# backplane_v1_0-smd.net
KiCad netlist of a schematic drawn in EAGLE
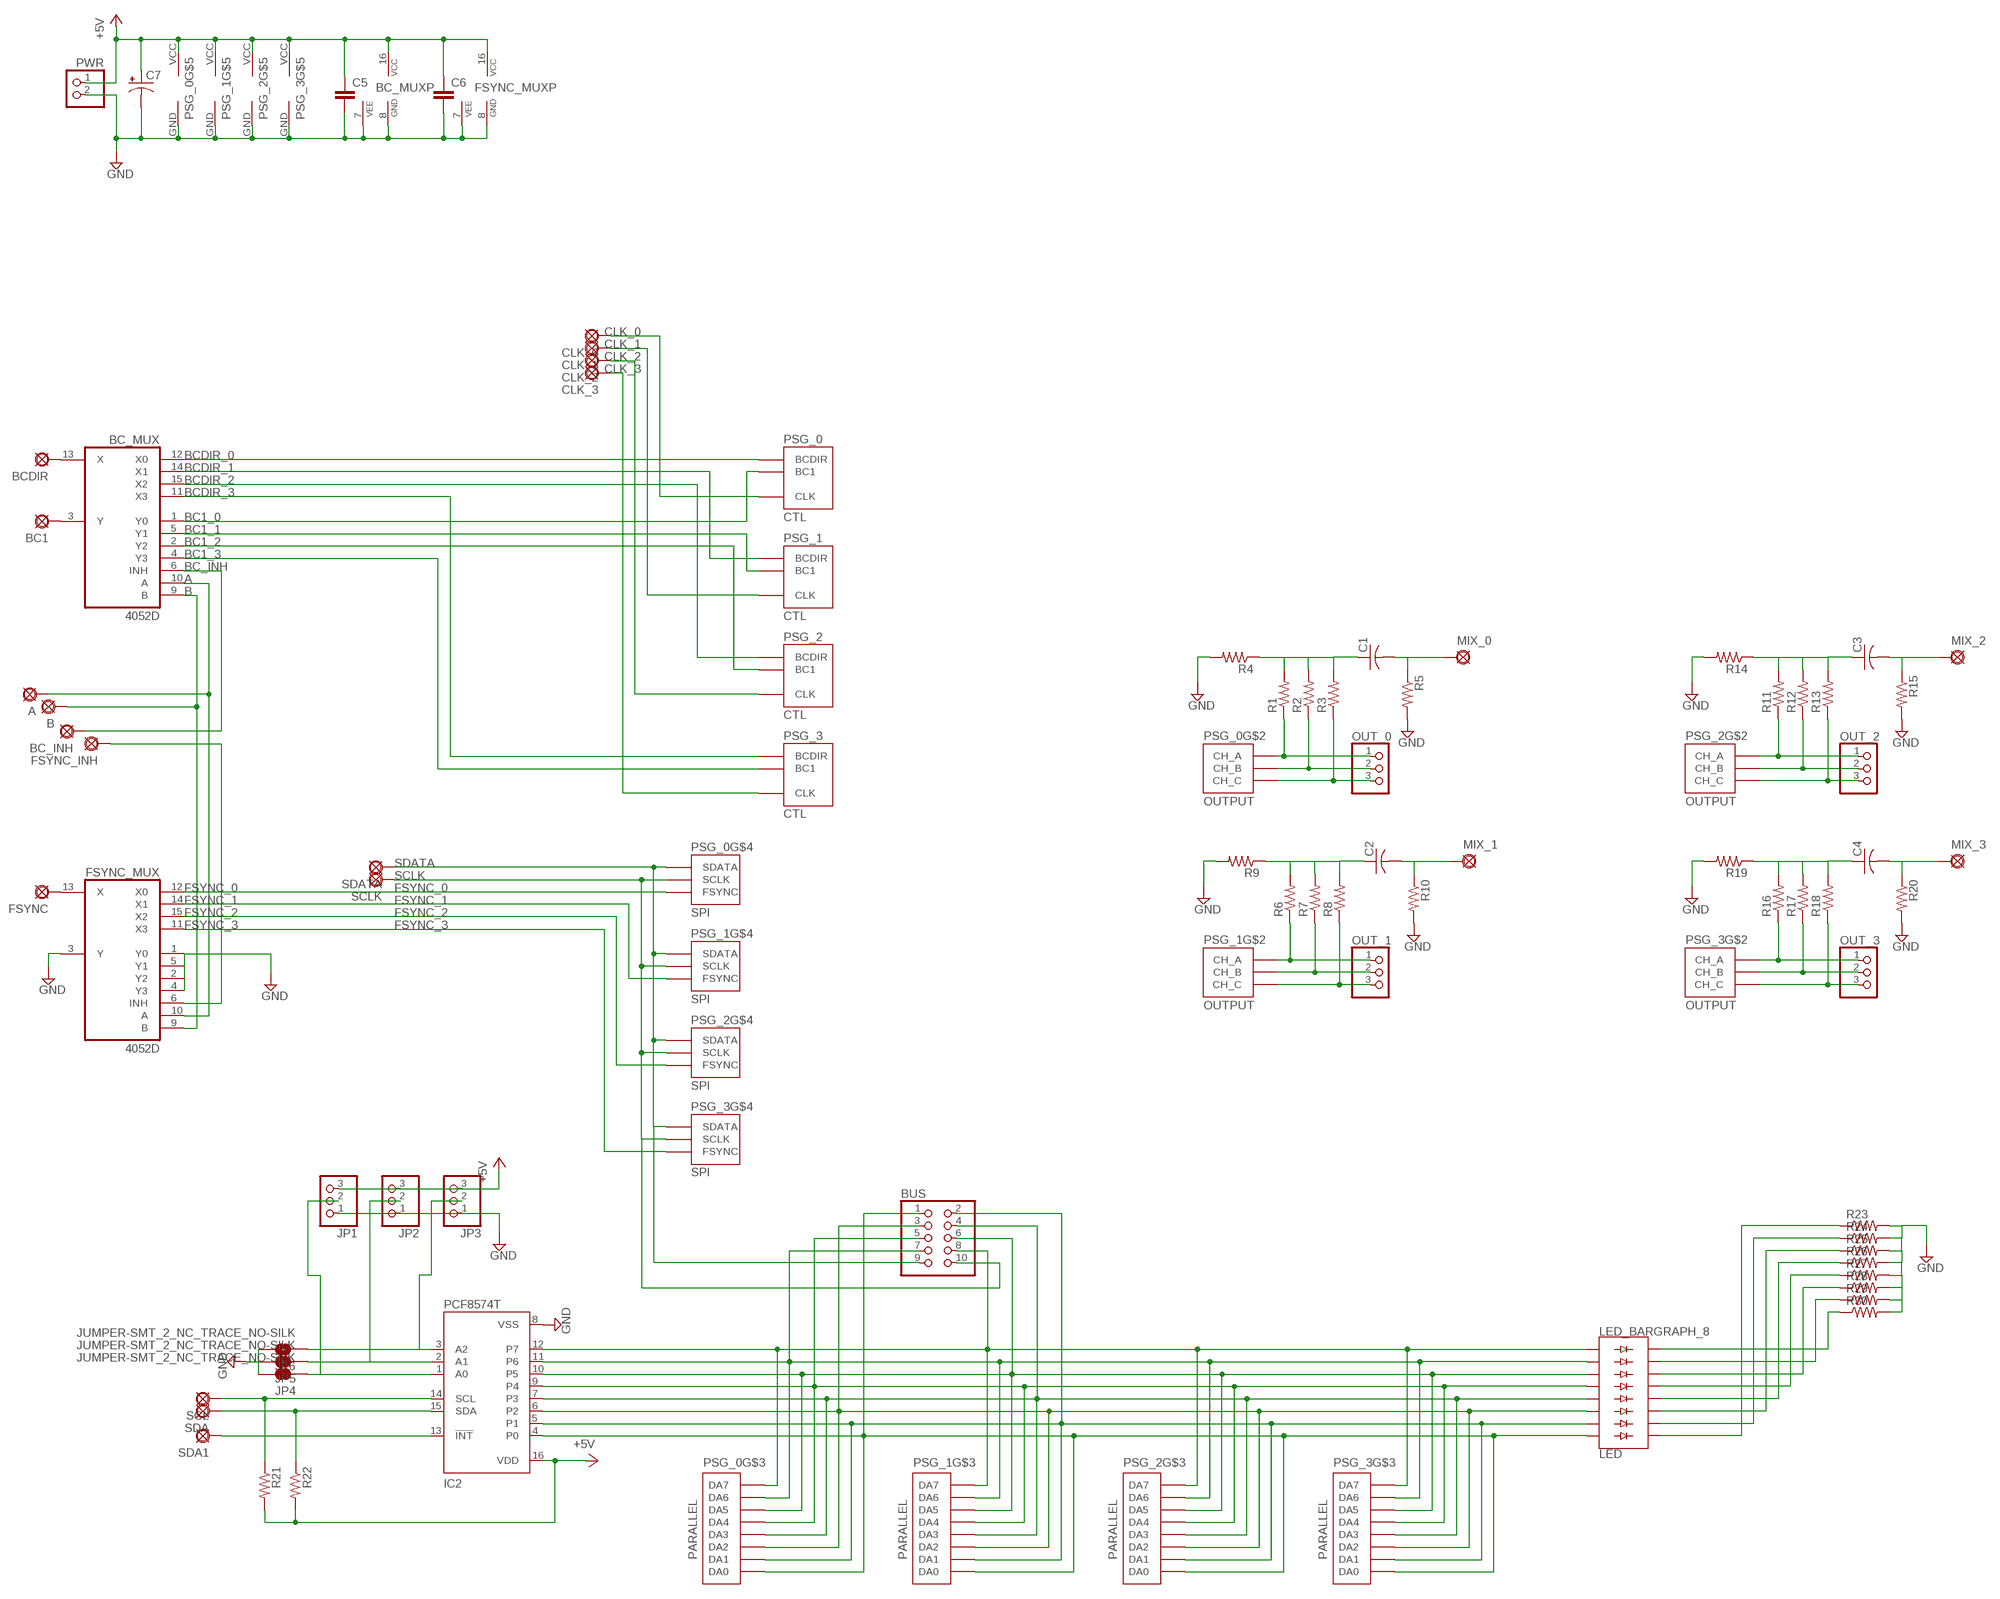
[diagram p0: schematic, sheet 1]

(export (version "E")
  (design (tool "Eeschema 10.0.6"))
  (components
    (comp (ref "A")
      (value "PAD")
      (footprint "eagle-import:SQUARE")
      (libsource (lib "eagle-import") (part "PAD"))
    )
    (comp (ref "B")
      (value "PAD")
      (footprint "eagle-import:SQUARE")
      (libsource (lib "eagle-import") (part "PAD"))
    )
    (comp (ref "BC1")
      (value "PAD")
      (footprint "eagle-import:SQUARE")
      (libsource (lib "eagle-import") (part "PAD"))
    )
    (comp (ref "BCDIR")
      (value "PAD")
      (footprint "eagle-import:SQUARE")
      (libsource (lib "eagle-import") (part "PAD"))
    )
    (comp (ref "BC_INH")
      (value "PAD")
      (footprint "eagle-import:SQUARE")
      (libsource (lib "eagle-import") (part "PAD"))
    )
    (comp (ref "BC_MUX")
      (value "4052D")
      (footprint "eagle-import:SO16")
      (libsource (lib "eagle-import") (part "4052D"))
    )
    (comp (ref "BUS")
      (value "PINHD-2X5IDC")
      (footprint "eagle-import:10PIN_IDC")
      (libsource (lib "eagle-import") (part "PINHD-2X5IDC"))
    )
    (comp (ref "C1")
      (value "C-USC0805")
      (footprint "eagle-import:C0805")
      (libsource (lib "eagle-import") (part "C-USC0805"))
    )
    (comp (ref "C2")
      (value "C-USC0805")
      (footprint "eagle-import:C0805")
      (libsource (lib "eagle-import") (part "C-USC0805"))
    )
    (comp (ref "C3")
      (value "C-USC0805")
      (footprint "eagle-import:C0805")
      (libsource (lib "eagle-import") (part "C-USC0805"))
    )
    (comp (ref "C4")
      (value "C-USC0805")
      (footprint "eagle-import:C0805")
      (libsource (lib "eagle-import") (part "C-USC0805"))
    )
    (comp (ref "C5")
      (value "050X030_0251")
      (footprint "eagle-import:050X030_025")
      (libsource (lib "eagle-import") (part "050X030_0251"))
    )
    (comp (ref "C6")
      (value "050X030_0251")
      (footprint "eagle-import:050X030_025")
      (libsource (lib "eagle-import") (part "050X030_0251"))
    )
    (comp (ref "C7")
      (value "0631")
      (footprint "eagle-import:063_025")
      (libsource (lib "eagle-import") (part "0631"))
    )
    (comp (ref "CLK_0")
      (value "PAD")
      (footprint "eagle-import:SQUARE")
      (libsource (lib "eagle-import") (part "PAD"))
    )
    (comp (ref "CLK_1")
      (value "PAD")
      (footprint "eagle-import:SQUARE")
      (libsource (lib "eagle-import") (part "PAD"))
    )
    (comp (ref "CLK_2")
      (value "PAD")
      (footprint "eagle-import:SQUARE")
      (libsource (lib "eagle-import") (part "PAD"))
    )
    (comp (ref "CLK_3")
      (value "PAD")
      (footprint "eagle-import:SQUARE")
      (libsource (lib "eagle-import") (part "PAD"))
    )
    (comp (ref "FSYNC")
      (value "PAD")
      (footprint "eagle-import:SQUARE")
      (libsource (lib "eagle-import") (part "PAD"))
    )
    (comp (ref "FSYNC_INH")
      (value "PAD")
      (footprint "eagle-import:SQUARE")
      (libsource (lib "eagle-import") (part "PAD"))
    )
    (comp (ref "FSYNC_MUX")
      (value "4052D")
      (footprint "eagle-import:SO16")
      (libsource (lib "eagle-import") (part "4052D"))
    )
    (comp (ref "IC2")
      (value "PCF8574T")
      (footprint "eagle-import:SO16W")
      (fields (field (name "MPN") "PCF8574T/3,512"))
      (libsource (lib "eagle-import") (part "PCF8574T"))
    )
    (comp (ref "JP1")
      (value "PINHD-1X3")
      (footprint "eagle-import:1X03")
      (libsource (lib "eagle-import") (part "PINHD-1X3"))
    )
    (comp (ref "JP2")
      (value "PINHD-1X3")
      (footprint "eagle-import:1X03")
      (libsource (lib "eagle-import") (part "PINHD-1X3"))
    )
    (comp (ref "JP3")
      (value "PINHD-1X3")
      (footprint "eagle-import:1X03")
      (libsource (lib "eagle-import") (part "PINHD-1X3"))
    )
    (comp (ref "JP4")
      (value "JUMPER-SMT_2_NC_TRACE_NO-SILK")
      (footprint "eagle-import:SMT-JUMPER_2_NC_TRACE_NO-SILK")
      (libsource (lib "eagle-import") (part "JUMPER-SMT_2_NC_TRACE_NO-SILK"))
    )
    (comp (ref "JP5")
      (value "JUMPER-SMT_2_NC_TRACE_NO-SILK")
      (footprint "eagle-import:SMT-JUMPER_2_NC_TRACE_NO-SILK")
      (libsource (lib "eagle-import") (part "JUMPER-SMT_2_NC_TRACE_NO-SILK"))
    )
    (comp (ref "JP6")
      (value "JUMPER-SMT_2_NC_TRACE_NO-SILK")
      (footprint "eagle-import:SMT-JUMPER_2_NC_TRACE_NO-SILK")
      (libsource (lib "eagle-import") (part "JUMPER-SMT_2_NC_TRACE_NO-SILK"))
    )
    (comp (ref "LED")
      (value "LED_BARGRAPH_8")
      (footprint "eagle-import:LED_BARGRAPH_8")
      (libsource (lib "eagle-import") (part "LED_BARGRAPH_8"))
    )
    (comp (ref "MIX_0")
      (value "PAD")
      (footprint "eagle-import:SQUARE")
      (libsource (lib "eagle-import") (part "PAD"))
    )
    (comp (ref "MIX_1")
      (value "PAD")
      (footprint "eagle-import:SQUARE")
      (libsource (lib "eagle-import") (part "PAD"))
    )
    (comp (ref "MIX_2")
      (value "PAD")
      (footprint "eagle-import:SQUARE")
      (libsource (lib "eagle-import") (part "PAD"))
    )
    (comp (ref "MIX_3")
      (value "PAD")
      (footprint "eagle-import:SQUARE")
      (libsource (lib "eagle-import") (part "PAD"))
    )
    (comp (ref "OUT_0")
      (value "PINHD-1X3")
      (footprint "eagle-import:1X03")
      (libsource (lib "eagle-import") (part "PINHD-1X3"))
    )
    (comp (ref "OUT_1")
      (value "PINHD-1X3")
      (footprint "eagle-import:1X03")
      (libsource (lib "eagle-import") (part "PINHD-1X3"))
    )
    (comp (ref "OUT_2")
      (value "PINHD-1X3")
      (footprint "eagle-import:1X03")
      (libsource (lib "eagle-import") (part "PINHD-1X3"))
    )
    (comp (ref "OUT_3")
      (value "PINHD-1X3")
      (footprint "eagle-import:1X03")
      (libsource (lib "eagle-import") (part "PINHD-1X3"))
    )
    (comp (ref "PSG_0")
      (value "PSG_DAUGHTER")
      (footprint "eagle-import:PSG_DAUGHTER")
      (libsource (lib "eagle-import") (part "PSG_DAUGHTER"))
    )
    (comp (ref "PSG_1")
      (value "PSG_DAUGHTER")
      (footprint "eagle-import:PSG_DAUGHTER")
      (libsource (lib "eagle-import") (part "PSG_DAUGHTER"))
    )
    (comp (ref "PSG_2")
      (value "PSG_DAUGHTER")
      (footprint "eagle-import:PSG_DAUGHTER")
      (libsource (lib "eagle-import") (part "PSG_DAUGHTER"))
    )
    (comp (ref "PSG_3")
      (value "PSG_DAUGHTER")
      (footprint "eagle-import:PSG_DAUGHTER")
      (libsource (lib "eagle-import") (part "PSG_DAUGHTER"))
    )
    (comp (ref "PWR")
      (value "PINHD-1X2")
      (footprint "eagle-import:1X02")
      (libsource (lib "eagle-import") (part "PINHD-1X2"))
    )
    (comp (ref "R1")
      (value "R-US_R0805")
      (footprint "eagle-import:R0805")
      (libsource (lib "eagle-import") (part "R-US_R0805"))
    )
    (comp (ref "R2")
      (value "R-US_R0805")
      (footprint "eagle-import:R0805")
      (libsource (lib "eagle-import") (part "R-US_R0805"))
    )
    (comp (ref "R3")
      (value "R-US_R0805")
      (footprint "eagle-import:R0805")
      (libsource (lib "eagle-import") (part "R-US_R0805"))
    )
    (comp (ref "R4")
      (value "R-US_R0805")
      (footprint "eagle-import:R0805")
      (libsource (lib "eagle-import") (part "R-US_R0805"))
    )
    (comp (ref "R5")
      (value "R-US_R0805")
      (footprint "eagle-import:R0805")
      (libsource (lib "eagle-import") (part "R-US_R0805"))
    )
    (comp (ref "R6")
      (value "R-US_R0805")
      (footprint "eagle-import:R0805")
      (libsource (lib "eagle-import") (part "R-US_R0805"))
    )
    (comp (ref "R7")
      (value "R-US_R0805")
      (footprint "eagle-import:R0805")
      (libsource (lib "eagle-import") (part "R-US_R0805"))
    )
    (comp (ref "R8")
      (value "R-US_R0805")
      (footprint "eagle-import:R0805")
      (libsource (lib "eagle-import") (part "R-US_R0805"))
    )
    (comp (ref "R9")
      (value "R-US_R0805")
      (footprint "eagle-import:R0805")
      (libsource (lib "eagle-import") (part "R-US_R0805"))
    )
    (comp (ref "R10")
      (value "R-US_R0805")
      (footprint "eagle-import:R0805")
      (libsource (lib "eagle-import") (part "R-US_R0805"))
    )
    (comp (ref "R11")
      (value "R-US_R0805")
      (footprint "eagle-import:R0805")
      (libsource (lib "eagle-import") (part "R-US_R0805"))
    )
    (comp (ref "R12")
      (value "R-US_R0805")
      (footprint "eagle-import:R0805")
      (libsource (lib "eagle-import") (part "R-US_R0805"))
    )
    (comp (ref "R13")
      (value "R-US_R0805")
      (footprint "eagle-import:R0805")
      (libsource (lib "eagle-import") (part "R-US_R0805"))
    )
    (comp (ref "R14")
      (value "R-US_R0805")
      (footprint "eagle-import:R0805")
      (libsource (lib "eagle-import") (part "R-US_R0805"))
    )
    (comp (ref "R15")
      (value "R-US_R0805")
      (footprint "eagle-import:R0805")
      (libsource (lib "eagle-import") (part "R-US_R0805"))
    )
    (comp (ref "R16")
      (value "R-US_R0805")
      (footprint "eagle-import:R0805")
      (libsource (lib "eagle-import") (part "R-US_R0805"))
    )
    (comp (ref "R17")
      (value "R-US_R0805")
      (footprint "eagle-import:R0805")
      (libsource (lib "eagle-import") (part "R-US_R0805"))
    )
    (comp (ref "R18")
      (value "R-US_R0805")
      (footprint "eagle-import:R0805")
      (libsource (lib "eagle-import") (part "R-US_R0805"))
    )
    (comp (ref "R19")
      (value "R-US_R0805")
      (footprint "eagle-import:R0805")
      (libsource (lib "eagle-import") (part "R-US_R0805"))
    )
    (comp (ref "R20")
      (value "R-US_R0805")
      (footprint "eagle-import:R0805")
      (libsource (lib "eagle-import") (part "R-US_R0805"))
    )
    (comp (ref "R21")
      (value "R-US_R0805")
      (footprint "eagle-import:R0805")
      (libsource (lib "eagle-import") (part "R-US_R0805"))
    )
    (comp (ref "R22")
      (value "R-US_R0805")
      (footprint "eagle-import:R0805")
      (libsource (lib "eagle-import") (part "R-US_R0805"))
    )
    (comp (ref "R23")
      (value "R-US_R0805")
      (footprint "eagle-import:R0805")
      (libsource (lib "eagle-import") (part "R-US_R0805"))
    )
    (comp (ref "R24")
      (value "R-US_R0805")
      (footprint "eagle-import:R0805")
      (libsource (lib "eagle-import") (part "R-US_R0805"))
    )
    (comp (ref "R25")
      (value "R-US_R0805")
      (footprint "eagle-import:R0805")
      (libsource (lib "eagle-import") (part "R-US_R0805"))
    )
    (comp (ref "R26")
      (value "R-US_R0805")
      (footprint "eagle-import:R0805")
      (libsource (lib "eagle-import") (part "R-US_R0805"))
    )
    (comp (ref "R27")
      (value "R-US_R0805")
      (footprint "eagle-import:R0805")
      (libsource (lib "eagle-import") (part "R-US_R0805"))
    )
    (comp (ref "R28")
      (value "R-US_R0805")
      (footprint "eagle-import:R0805")
      (libsource (lib "eagle-import") (part "R-US_R0805"))
    )
    (comp (ref "R29")
      (value "R-US_R0805")
      (footprint "eagle-import:R0805")
      (libsource (lib "eagle-import") (part "R-US_R0805"))
    )
    (comp (ref "R30")
      (value "R-US_R0805")
      (footprint "eagle-import:R0805")
      (libsource (lib "eagle-import") (part "R-US_R0805"))
    )
    (comp (ref "SCL")
      (value "PAD")
      (footprint "eagle-import:SQUARE")
      (libsource (lib "eagle-import") (part "PAD"))
    )
    (comp (ref "SCLK")
      (value "PAD")
      (footprint "eagle-import:SQUARE")
      (libsource (lib "eagle-import") (part "PAD"))
    )
    (comp (ref "SDA")
      (value "PAD")
      (footprint "eagle-import:SQUARE")
      (libsource (lib "eagle-import") (part "PAD"))
    )
    (comp (ref "SDA1")
      (value "PAD")
      (footprint "eagle-import:SQUARE")
      (libsource (lib "eagle-import") (part "PAD"))
    )
    (comp (ref "SDATA")
      (value "PAD")
      (footprint "eagle-import:SQUARE")
      (libsource (lib "eagle-import") (part "PAD"))
    )
  )
  (nets
    (net (code "1") (name "+5V") (class "Default")
      (node (ref "BC_MUX") (pin "16") (pinfunction "VCC_16") (pintype "power_in"))
      (node (ref "C5") (pin "1") (pinfunction "1_1") (pintype "passive"))
      (node (ref "C6") (pin "1") (pinfunction "1_1") (pintype "passive"))
      (node (ref "C7") (pin "+") (pinfunction "+_+") (pintype "passive"))
      (node (ref "FSYNC_MUX") (pin "16") (pinfunction "VCC_16") (pintype "power_in"))
      (node (ref "IC2") (pin "16") (pinfunction "VDD_16") (pintype "power_in"))
      (node (ref "JP1") (pin "3") (pinfunction "3_3") (pintype "passive"))
      (node (ref "JP2") (pin "3") (pinfunction "3_3") (pintype "passive"))
      (node (ref "JP3") (pin "3") (pinfunction "3_3") (pintype "passive"))
      (node (ref "PSG_0") (pin "VCC") (pinfunction "VCC_VCC") (pintype "power_in"))
      (node (ref "PSG_1") (pin "VCC") (pinfunction "VCC_VCC") (pintype "power_in"))
      (node (ref "PSG_2") (pin "VCC") (pinfunction "VCC_VCC") (pintype "power_in"))
      (node (ref "PSG_3") (pin "VCC") (pinfunction "VCC_VCC") (pintype "power_in"))
      (node (ref "PWR") (pin "1") (pinfunction "1_1") (pintype "passive"))
      (node (ref "R21") (pin "2") (pinfunction "2_2") (pintype "passive"))
      (node (ref "R22") (pin "2") (pinfunction "2_2") (pintype "passive"))
    )
    (net (code "2") (name "/A") (class "Default")
      (node (ref "A") (pin "1") (pinfunction "PAD_1") (pintype "passive"))
      (node (ref "BC_MUX") (pin "10") (pinfunction "A_10") (pintype "input"))
      (node (ref "FSYNC_MUX") (pin "10") (pinfunction "A_10") (pintype "input"))
    )
    (net (code "3") (name "/B") (class "Default")
      (node (ref "B") (pin "1") (pinfunction "PAD_1") (pintype "passive"))
      (node (ref "BC_MUX") (pin "9") (pinfunction "B_9") (pintype "input"))
      (node (ref "FSYNC_MUX") (pin "9") (pinfunction "B_9") (pintype "input"))
    )
    (net (code "4") (name "/BC1_0") (class "Default")
      (node (ref "BC_MUX") (pin "1") (pinfunction "Y0_1") (pintype "bidirectional"))
      (node (ref "PSG_0") (pin "BC1") (pinfunction "BC1_BC1") (pintype "input"))
    )
    (net (code "5") (name "/BC1_1") (class "Default")
      (node (ref "BC_MUX") (pin "5") (pinfunction "Y1_5") (pintype "bidirectional"))
      (node (ref "PSG_1") (pin "BC1") (pinfunction "BC1_BC1") (pintype "input"))
    )
    (net (code "6") (name "/BC1_2") (class "Default")
      (node (ref "BC_MUX") (pin "2") (pinfunction "Y2_2") (pintype "bidirectional"))
      (node (ref "PSG_2") (pin "BC1") (pinfunction "BC1_BC1") (pintype "input"))
    )
    (net (code "7") (name "/BC1_3") (class "Default")
      (node (ref "BC_MUX") (pin "4") (pinfunction "Y3_4") (pintype "bidirectional"))
      (node (ref "PSG_3") (pin "BC1") (pinfunction "BC1_BC1") (pintype "input"))
    )
    (net (code "8") (name "/BCDIR_0") (class "Default")
      (node (ref "BC_MUX") (pin "12") (pinfunction "X0_12") (pintype "bidirectional"))
      (node (ref "PSG_0") (pin "BCDIR") (pinfunction "BCDIR_BCDIR") (pintype "input"))
    )
    (net (code "9") (name "/BCDIR_1") (class "Default")
      (node (ref "BC_MUX") (pin "14") (pinfunction "X1_14") (pintype "bidirectional"))
      (node (ref "PSG_1") (pin "BCDIR") (pinfunction "BCDIR_BCDIR") (pintype "input"))
    )
    (net (code "10") (name "/BCDIR_2") (class "Default")
      (node (ref "BC_MUX") (pin "15") (pinfunction "X2_15") (pintype "bidirectional"))
      (node (ref "PSG_2") (pin "BCDIR") (pinfunction "BCDIR_BCDIR") (pintype "input"))
    )
    (net (code "11") (name "/BCDIR_3") (class "Default")
      (node (ref "BC_MUX") (pin "11") (pinfunction "X3_11") (pintype "bidirectional"))
      (node (ref "PSG_3") (pin "BCDIR") (pinfunction "BCDIR_BCDIR") (pintype "input"))
    )
    (net (code "12") (name "/BC_INH") (class "Default")
      (node (ref "BC_INH") (pin "1") (pinfunction "PAD_1") (pintype "passive"))
      (node (ref "BC_MUX") (pin "6") (pinfunction "INH_6") (pintype "input"))
    )
    (net (code "13") (name "/CLK_0") (class "Default")
      (node (ref "CLK_0") (pin "1") (pinfunction "PAD_1") (pintype "passive"))
      (node (ref "PSG_0") (pin "CLK") (pinfunction "CLK_CLK") (pintype "input"))
    )
    (net (code "14") (name "/CLK_1") (class "Default")
      (node (ref "CLK_1") (pin "1") (pinfunction "PAD_1") (pintype "passive"))
      (node (ref "PSG_1") (pin "CLK") (pinfunction "CLK_CLK") (pintype "input"))
    )
    (net (code "15") (name "/CLK_2") (class "Default")
      (node (ref "CLK_2") (pin "1") (pinfunction "PAD_1") (pintype "passive"))
      (node (ref "PSG_2") (pin "CLK") (pinfunction "CLK_CLK") (pintype "input"))
    )
    (net (code "16") (name "/CLK_3") (class "Default")
      (node (ref "CLK_3") (pin "1") (pinfunction "PAD_1") (pintype "passive"))
      (node (ref "PSG_3") (pin "CLK") (pinfunction "CLK_CLK") (pintype "input"))
    )
    (net (code "17") (name "/FSYNC_0") (class "Default")
      (node (ref "FSYNC_MUX") (pin "12") (pinfunction "X0_12") (pintype "bidirectional"))
      (node (ref "PSG_0") (pin "FSYNC") (pinfunction "FSYNC_FSYNC") (pintype "input"))
    )
    (net (code "18") (name "/FSYNC_1") (class "Default")
      (node (ref "FSYNC_MUX") (pin "14") (pinfunction "X1_14") (pintype "bidirectional"))
      (node (ref "PSG_1") (pin "FSYNC") (pinfunction "FSYNC_FSYNC") (pintype "input"))
    )
    (net (code "19") (name "/FSYNC_2") (class "Default")
      (node (ref "FSYNC_MUX") (pin "15") (pinfunction "X2_15") (pintype "bidirectional"))
      (node (ref "PSG_2") (pin "FSYNC") (pinfunction "FSYNC_FSYNC") (pintype "input"))
    )
    (net (code "20") (name "/FSYNC_3") (class "Default")
      (node (ref "FSYNC_MUX") (pin "11") (pinfunction "X3_11") (pintype "bidirectional"))
      (node (ref "PSG_3") (pin "FSYNC") (pinfunction "FSYNC_FSYNC") (pintype "input"))
    )
    (net (code "21") (name "/SCLK") (class "Default")
      (node (ref "BUS") (pin "10") (pinfunction "10_10") (pintype "passive"))
      (node (ref "PSG_0") (pin "SCLK") (pinfunction "SCLK_SCLK") (pintype "input"))
      (node (ref "PSG_1") (pin "SCLK") (pinfunction "SCLK_SCLK") (pintype "input"))
      (node (ref "PSG_2") (pin "SCLK") (pinfunction "SCLK_SCLK") (pintype "input"))
      (node (ref "PSG_3") (pin "SCLK") (pinfunction "SCLK_SCLK") (pintype "input"))
      (node (ref "SCLK") (pin "1") (pinfunction "PAD_1") (pintype "passive"))
    )
    (net (code "22") (name "/SDATA") (class "Default")
      (node (ref "BUS") (pin "9") (pinfunction "9_9") (pintype "passive"))
      (node (ref "PSG_0") (pin "SDATA") (pinfunction "SDATA_SDATA") (pintype "bidirectional"))
      (node (ref "PSG_1") (pin "SDATA") (pinfunction "SDATA_SDATA") (pintype "bidirectional"))
      (node (ref "PSG_2") (pin "SDATA") (pinfunction "SDATA_SDATA") (pintype "bidirectional"))
      (node (ref "PSG_3") (pin "SDATA") (pinfunction "SDATA_SDATA") (pintype "bidirectional"))
      (node (ref "SDATA") (pin "1") (pinfunction "PAD_1") (pintype "passive"))
    )
    (net (code "23") (name "GND") (class "Default")
      (node (ref "BC_MUX") (pin "7") (pinfunction "VEE_7") (pintype "power_in"))
      (node (ref "BC_MUX") (pin "8") (pinfunction "GND_8") (pintype "power_in"))
      (node (ref "C5") (pin "2") (pinfunction "2_2") (pintype "passive"))
      (node (ref "C6") (pin "2") (pinfunction "2_2") (pintype "passive"))
      (node (ref "C7") (pin "-") (pinfunction "-_-") (pintype "passive"))
      (node (ref "FSYNC_MUX") (pin "1") (pinfunction "Y0_1") (pintype "bidirectional"))
      (node (ref "FSYNC_MUX") (pin "2") (pinfunction "Y2_2") (pintype "bidirectional"))
      (node (ref "FSYNC_MUX") (pin "3") (pinfunction "Y_3") (pintype "bidirectional"))
      (node (ref "FSYNC_MUX") (pin "4") (pinfunction "Y3_4") (pintype "bidirectional"))
      (node (ref "FSYNC_MUX") (pin "5") (pinfunction "Y1_5") (pintype "bidirectional"))
      (node (ref "FSYNC_MUX") (pin "7") (pinfunction "VEE_7") (pintype "power_in"))
      (node (ref "FSYNC_MUX") (pin "8") (pinfunction "GND_8") (pintype "power_in"))
      (node (ref "IC2") (pin "8") (pinfunction "VSS_8") (pintype "power_in"))
      (node (ref "JP1") (pin "1") (pinfunction "1_1") (pintype "passive"))
      (node (ref "JP2") (pin "1") (pinfunction "1_1") (pintype "passive"))
      (node (ref "JP3") (pin "1") (pinfunction "1_1") (pintype "passive"))
      (node (ref "JP4") (pin "2") (pinfunction "2_2") (pintype "passive"))
      (node (ref "JP5") (pin "2") (pinfunction "2_2") (pintype "passive"))
      (node (ref "JP6") (pin "2") (pinfunction "2_2") (pintype "passive"))
      (node (ref "PSG_0") (pin "GND") (pinfunction "GND_GND") (pintype "power_in"))
      (node (ref "PSG_1") (pin "GND") (pinfunction "GND_GND") (pintype "power_in"))
      (node (ref "PSG_2") (pin "GND") (pinfunction "GND_GND") (pintype "power_in"))
      (node (ref "PSG_3") (pin "GND") (pinfunction "GND_GND") (pintype "power_in"))
      (node (ref "PWR") (pin "2") (pinfunction "2_2") (pintype "passive"))
      (node (ref "R10") (pin "2") (pinfunction "2_2") (pintype "passive"))
      (node (ref "R14") (pin "2") (pinfunction "2_2") (pintype "passive"))
      (node (ref "R15") (pin "2") (pinfunction "2_2") (pintype "passive"))
      (node (ref "R19") (pin "2") (pinfunction "2_2") (pintype "passive"))
      (node (ref "R20") (pin "2") (pinfunction "2_2") (pintype "passive"))
      (node (ref "R23") (pin "2") (pinfunction "2_2") (pintype "passive"))
      (node (ref "R24") (pin "2") (pinfunction "2_2") (pintype "passive"))
      (node (ref "R25") (pin "2") (pinfunction "2_2") (pintype "passive"))
      (node (ref "R26") (pin "2") (pinfunction "2_2") (pintype "passive"))
      (node (ref "R27") (pin "2") (pinfunction "2_2") (pintype "passive"))
      (node (ref "R28") (pin "2") (pinfunction "2_2") (pintype "passive"))
      (node (ref "R29") (pin "2") (pinfunction "2_2") (pintype "passive"))
      (node (ref "R30") (pin "2") (pinfunction "2_2") (pintype "passive"))
      (node (ref "R4") (pin "2") (pinfunction "2_2") (pintype "passive"))
      (node (ref "R5") (pin "2") (pinfunction "2_2") (pintype "passive"))
      (node (ref "R9") (pin "2") (pinfunction "2_2") (pintype "passive"))
    )
    (net (code "24") (name "Net-(BC1-PAD)") (class "Default")
      (node (ref "BC1") (pin "1") (pinfunction "PAD_1") (pintype "passive"))
      (node (ref "BC_MUX") (pin "3") (pinfunction "Y_3") (pintype "bidirectional"))
    )
    (net (code "25") (name "Net-(BCDIR-PAD)") (class "Default")
      (node (ref "BCDIR") (pin "1") (pinfunction "PAD_1") (pintype "passive"))
      (node (ref "BC_MUX") (pin "13") (pinfunction "X_13") (pintype "bidirectional"))
    )
    (net (code "26") (name "Net-(C1-Pad1)") (class "Default")
      (node (ref "C1") (pin "1") (pinfunction "1_1") (pintype "passive"))
      (node (ref "R1") (pin "2") (pinfunction "2_2") (pintype "passive"))
      (node (ref "R2") (pin "2") (pinfunction "2_2") (pintype "passive"))
      (node (ref "R3") (pin "2") (pinfunction "2_2") (pintype "passive"))
      (node (ref "R4") (pin "1") (pinfunction "1_1") (pintype "passive"))
    )
    (net (code "27") (name "Net-(C2-Pad1)") (class "Default")
      (node (ref "C2") (pin "1") (pinfunction "1_1") (pintype "passive"))
      (node (ref "R6") (pin "2") (pinfunction "2_2") (pintype "passive"))
      (node (ref "R7") (pin "2") (pinfunction "2_2") (pintype "passive"))
      (node (ref "R8") (pin "2") (pinfunction "2_2") (pintype "passive"))
      (node (ref "R9") (pin "1") (pinfunction "1_1") (pintype "passive"))
    )
    (net (code "28") (name "Net-(C3-Pad1)") (class "Default")
      (node (ref "C3") (pin "1") (pinfunction "1_1") (pintype "passive"))
      (node (ref "R11") (pin "2") (pinfunction "2_2") (pintype "passive"))
      (node (ref "R12") (pin "2") (pinfunction "2_2") (pintype "passive"))
      (node (ref "R13") (pin "2") (pinfunction "2_2") (pintype "passive"))
      (node (ref "R14") (pin "1") (pinfunction "1_1") (pintype "passive"))
    )
    (net (code "29") (name "Net-(C4-Pad1)") (class "Default")
      (node (ref "C4") (pin "1") (pinfunction "1_1") (pintype "passive"))
      (node (ref "R16") (pin "2") (pinfunction "2_2") (pintype "passive"))
      (node (ref "R17") (pin "2") (pinfunction "2_2") (pintype "passive"))
      (node (ref "R18") (pin "2") (pinfunction "2_2") (pintype "passive"))
      (node (ref "R19") (pin "1") (pinfunction "1_1") (pintype "passive"))
    )
    (net (code "30") (name "Net-(FSYNC-PAD)") (class "Default")
      (node (ref "FSYNC") (pin "1") (pinfunction "PAD_1") (pintype "passive"))
      (node (ref "FSYNC_MUX") (pin "13") (pinfunction "X_13") (pintype "bidirectional"))
    )
    (net (code "31") (name "Net-(FSYNC_INH-PAD)") (class "Default")
      (node (ref "FSYNC_INH") (pin "1") (pinfunction "PAD_1") (pintype "passive"))
      (node (ref "FSYNC_MUX") (pin "6") (pinfunction "INH_6") (pintype "input"))
    )
    (net (code "32") (name "Net-(IC2-A0)") (class "Default")
      (node (ref "IC2") (pin "1") (pinfunction "A0_1") (pintype "input"))
      (node (ref "JP1") (pin "2") (pinfunction "2_2") (pintype "passive"))
      (node (ref "JP4") (pin "1") (pinfunction "1_1") (pintype "passive"))
    )
    (net (code "33") (name "Net-(IC2-A1)") (class "Default")
      (node (ref "IC2") (pin "2") (pinfunction "A1_2") (pintype "input"))
      (node (ref "JP2") (pin "2") (pinfunction "2_2") (pintype "passive"))
      (node (ref "JP5") (pin "1") (pinfunction "1_1") (pintype "passive"))
    )
    (net (code "34") (name "Net-(IC2-A2)") (class "Default")
      (node (ref "IC2") (pin "3") (pinfunction "A2_3") (pintype "input"))
      (node (ref "JP3") (pin "2") (pinfunction "2_2") (pintype "passive"))
      (node (ref "JP6") (pin "1") (pinfunction "1_1") (pintype "passive"))
    )
    (net (code "35") (name "Net-(IC2-P0)") (class "Default")
      (node (ref "BUS") (pin "1") (pinfunction "1_1") (pintype "passive"))
      (node (ref "IC2") (pin "4") (pinfunction "P0_4") (pintype "bidirectional"))
      (node (ref "LED") (pin "A0") (pinfunction "A0_A0") (pintype "passive"))
      (node (ref "PSG_0") (pin "DA0") (pinfunction "DA0_DA0") (pintype "bidirectional"))
      (node (ref "PSG_1") (pin "DA0") (pinfunction "DA0_DA0") (pintype "bidirectional"))
      (node (ref "PSG_2") (pin "DA0") (pinfunction "DA0_DA0") (pintype "bidirectional"))
      (node (ref "PSG_3") (pin "DA0") (pinfunction "DA0_DA0") (pintype "bidirectional"))
    )
    (net (code "36") (name "Net-(IC2-P1)") (class "Default")
      (node (ref "BUS") (pin "2") (pinfunction "2_2") (pintype "passive"))
      (node (ref "IC2") (pin "5") (pinfunction "P1_5") (pintype "bidirectional"))
      (node (ref "LED") (pin "A1") (pinfunction "A1_A1") (pintype "passive"))
      (node (ref "PSG_0") (pin "DA1") (pinfunction "DA1_DA1") (pintype "bidirectional"))
      (node (ref "PSG_1") (pin "DA1") (pinfunction "DA1_DA1") (pintype "bidirectional"))
      (node (ref "PSG_2") (pin "DA1") (pinfunction "DA1_DA1") (pintype "bidirectional"))
      (node (ref "PSG_3") (pin "DA1") (pinfunction "DA1_DA1") (pintype "bidirectional"))
    )
    (net (code "37") (name "Net-(IC2-P2)") (class "Default")
      (node (ref "BUS") (pin "3") (pinfunction "3_3") (pintype "passive"))
      (node (ref "IC2") (pin "6") (pinfunction "P2_6") (pintype "bidirectional"))
      (node (ref "LED") (pin "A2") (pinfunction "A2_A2") (pintype "passive"))
      (node (ref "PSG_0") (pin "DA2") (pinfunction "DA2_DA2") (pintype "bidirectional"))
      (node (ref "PSG_1") (pin "DA2") (pinfunction "DA2_DA2") (pintype "bidirectional"))
      (node (ref "PSG_2") (pin "DA2") (pinfunction "DA2_DA2") (pintype "bidirectional"))
      (node (ref "PSG_3") (pin "DA2") (pinfunction "DA2_DA2") (pintype "bidirectional"))
    )
    (net (code "38") (name "Net-(IC2-P3)") (class "Default")
      (node (ref "BUS") (pin "4") (pinfunction "4_4") (pintype "passive"))
      (node (ref "IC2") (pin "7") (pinfunction "P3_7") (pintype "bidirectional"))
      (node (ref "LED") (pin "A3") (pinfunction "A3_A3") (pintype "passive"))
      (node (ref "PSG_0") (pin "DA3") (pinfunction "DA3_DA3") (pintype "bidirectional"))
      (node (ref "PSG_1") (pin "DA3") (pinfunction "DA3_DA3") (pintype "bidirectional"))
      (node (ref "PSG_2") (pin "DA3") (pinfunction "DA3_DA3") (pintype "bidirectional"))
      (node (ref "PSG_3") (pin "DA3") (pinfunction "DA3_DA3") (pintype "bidirectional"))
    )
    (net (code "39") (name "Net-(IC2-P4)") (class "Default")
      (node (ref "BUS") (pin "5") (pinfunction "5_5") (pintype "passive"))
      (node (ref "IC2") (pin "9") (pinfunction "P4_9") (pintype "bidirectional"))
      (node (ref "LED") (pin "A4") (pinfunction "A4_A4") (pintype "passive"))
      (node (ref "PSG_0") (pin "DA4") (pinfunction "DA4_DA4") (pintype "bidirectional"))
      (node (ref "PSG_1") (pin "DA4") (pinfunction "DA4_DA4") (pintype "bidirectional"))
      (node (ref "PSG_2") (pin "DA4") (pinfunction "DA4_DA4") (pintype "bidirectional"))
      (node (ref "PSG_3") (pin "DA4") (pinfunction "DA4_DA4") (pintype "bidirectional"))
    )
    (net (code "40") (name "Net-(IC2-P5)") (class "Default")
      (node (ref "BUS") (pin "6") (pinfunction "6_6") (pintype "passive"))
      (node (ref "IC2") (pin "10") (pinfunction "P5_10") (pintype "bidirectional"))
      (node (ref "LED") (pin "A5") (pinfunction "A5_A5") (pintype "passive"))
      (node (ref "PSG_0") (pin "DA5") (pinfunction "DA5_DA5") (pintype "bidirectional"))
      (node (ref "PSG_1") (pin "DA5") (pinfunction "DA5_DA5") (pintype "bidirectional"))
      (node (ref "PSG_2") (pin "DA5") (pinfunction "DA5_DA5") (pintype "bidirectional"))
      (node (ref "PSG_3") (pin "DA5") (pinfunction "DA5_DA5") (pintype "bidirectional"))
    )
    (net (code "41") (name "Net-(IC2-P6)") (class "Default")
      (node (ref "BUS") (pin "7") (pinfunction "7_7") (pintype "passive"))
      (node (ref "IC2") (pin "11") (pinfunction "P6_11") (pintype "bidirectional"))
      (node (ref "LED") (pin "A6") (pinfunction "A6_A6") (pintype "passive"))
      (node (ref "PSG_0") (pin "DA6") (pinfunction "DA6_DA6") (pintype "bidirectional"))
      (node (ref "PSG_1") (pin "DA6") (pinfunction "DA6_DA6") (pintype "bidirectional"))
      (node (ref "PSG_2") (pin "DA6") (pinfunction "DA6_DA6") (pintype "bidirectional"))
      (node (ref "PSG_3") (pin "DA6") (pinfunction "DA6_DA6") (pintype "bidirectional"))
    )
    (net (code "42") (name "Net-(IC2-P7)") (class "Default")
      (node (ref "BUS") (pin "8") (pinfunction "8_8") (pintype "passive"))
      (node (ref "IC2") (pin "12") (pinfunction "P7_12") (pintype "bidirectional"))
      (node (ref "LED") (pin "A7") (pinfunction "A7_A7") (pintype "passive"))
      (node (ref "PSG_0") (pin "DA7") (pinfunction "DA7_DA7") (pintype "bidirectional"))
      (node (ref "PSG_1") (pin "DA7") (pinfunction "DA7_DA7") (pintype "bidirectional"))
      (node (ref "PSG_2") (pin "DA7") (pinfunction "DA7_DA7") (pintype "bidirectional"))
      (node (ref "PSG_3") (pin "DA7") (pinfunction "DA7_DA7") (pintype "bidirectional"))
    )
    (net (code "43") (name "Net-(IC2-SCL)") (class "Default")
      (node (ref "IC2") (pin "14") (pinfunction "SCL_14") (pintype "input"))
      (node (ref "R21") (pin "1") (pinfunction "1_1") (pintype "passive"))
      (node (ref "SCL") (pin "1") (pinfunction "PAD_1") (pintype "passive"))
    )
    (net (code "44") (name "Net-(IC2-SDA)") (class "Default")
      (node (ref "IC2") (pin "15") (pinfunction "SDA_15") (pintype "bidirectional"))
      (node (ref "R22") (pin "1") (pinfunction "1_1") (pintype "passive"))
      (node (ref "SDA") (pin "1") (pinfunction "PAD_1") (pintype "passive"))
    )
    (net (code "45") (name "Net-(IC2-~{INT})") (class "Default")
      (node (ref "IC2") (pin "13") (pinfunction "~{INT}_13") (pintype "output"))
      (node (ref "SDA1") (pin "1") (pinfunction "PAD_1") (pintype "passive"))
    )
    (net (code "46") (name "Net-(LED-PadC0)") (class "Default")
      (node (ref "LED") (pin "C0") (pinfunction "C0_C0") (pintype "passive"))
      (node (ref "R23") (pin "1") (pinfunction "1_1") (pintype "passive"))
    )
    (net (code "47") (name "Net-(LED-PadC1)") (class "Default")
      (node (ref "LED") (pin "C1") (pinfunction "C1_C1") (pintype "passive"))
      (node (ref "R24") (pin "1") (pinfunction "1_1") (pintype "passive"))
    )
    (net (code "48") (name "Net-(LED-PadC2)") (class "Default")
      (node (ref "LED") (pin "C2") (pinfunction "C2_C2") (pintype "passive"))
      (node (ref "R25") (pin "1") (pinfunction "1_1") (pintype "passive"))
    )
    (net (code "49") (name "Net-(LED-PadC3)") (class "Default")
      (node (ref "LED") (pin "C3") (pinfunction "C3_C3") (pintype "passive"))
      (node (ref "R26") (pin "1") (pinfunction "1_1") (pintype "passive"))
    )
    (net (code "50") (name "Net-(LED-PadC4)") (class "Default")
      (node (ref "LED") (pin "C4") (pinfunction "C4_C4") (pintype "passive"))
      (node (ref "R27") (pin "1") (pinfunction "1_1") (pintype "passive"))
    )
    (net (code "51") (name "Net-(LED-PadC5)") (class "Default")
      (node (ref "LED") (pin "C5") (pinfunction "C5_C5") (pintype "passive"))
      (node (ref "R28") (pin "1") (pinfunction "1_1") (pintype "passive"))
    )
    (net (code "52") (name "Net-(LED-PadC6)") (class "Default")
      (node (ref "LED") (pin "C6") (pinfunction "C6_C6") (pintype "passive"))
      (node (ref "R29") (pin "1") (pinfunction "1_1") (pintype "passive"))
    )
    (net (code "53") (name "Net-(LED-PadC7)") (class "Default")
      (node (ref "LED") (pin "C7") (pinfunction "C7_C7") (pintype "passive"))
      (node (ref "R30") (pin "1") (pinfunction "1_1") (pintype "passive"))
    )
    (net (code "54") (name "Net-(MIX_0-PAD)") (class "Default")
      (node (ref "C1") (pin "2") (pinfunction "2_2") (pintype "passive"))
      (node (ref "MIX_0") (pin "1") (pinfunction "PAD_1") (pintype "passive"))
      (node (ref "R5") (pin "1") (pinfunction "1_1") (pintype "passive"))
    )
    (net (code "55") (name "Net-(MIX_1-PAD)") (class "Default")
      (node (ref "C2") (pin "2") (pinfunction "2_2") (pintype "passive"))
      (node (ref "MIX_1") (pin "1") (pinfunction "PAD_1") (pintype "passive"))
      (node (ref "R10") (pin "1") (pinfunction "1_1") (pintype "passive"))
    )
    (net (code "56") (name "Net-(MIX_2-PAD)") (class "Default")
      (node (ref "C3") (pin "2") (pinfunction "2_2") (pintype "passive"))
      (node (ref "MIX_2") (pin "1") (pinfunction "PAD_1") (pintype "passive"))
      (node (ref "R15") (pin "1") (pinfunction "1_1") (pintype "passive"))
    )
    (net (code "57") (name "Net-(MIX_3-PAD)") (class "Default")
      (node (ref "C4") (pin "2") (pinfunction "2_2") (pintype "passive"))
      (node (ref "MIX_3") (pin "1") (pinfunction "PAD_1") (pintype "passive"))
      (node (ref "R20") (pin "1") (pinfunction "1_1") (pintype "passive"))
    )
    (net (code "58") (name "Net-(PSG_0B-CH_A)") (class "Default")
      (node (ref "OUT_0") (pin "1") (pinfunction "1_1") (pintype "passive"))
      (node (ref "PSG_0") (pin "OUT_A") (pinfunction "CH_A_OUT_A") (pintype "input"))
      (node (ref "R1") (pin "1") (pinfunction "1_1") (pintype "passive"))
    )
    (net (code "59") (name "Net-(PSG_0B-CH_B)") (class "Default")
      (node (ref "OUT_0") (pin "2") (pinfunction "2_2") (pintype "passive"))
      (node (ref "PSG_0") (pin "OUT_B") (pinfunction "CH_B_OUT_B") (pintype "input"))
      (node (ref "R2") (pin "1") (pinfunction "1_1") (pintype "passive"))
    )
    (net (code "60") (name "Net-(PSG_0B-CH_C)") (class "Default")
      (node (ref "OUT_0") (pin "3") (pinfunction "3_3") (pintype "passive"))
      (node (ref "PSG_0") (pin "OUT_C") (pinfunction "CH_C_OUT_C") (pintype "input"))
      (node (ref "R3") (pin "1") (pinfunction "1_1") (pintype "passive"))
    )
    (net (code "61") (name "Net-(PSG_1B-CH_A)") (class "Default")
      (node (ref "OUT_1") (pin "1") (pinfunction "1_1") (pintype "passive"))
      (node (ref "PSG_1") (pin "OUT_A") (pinfunction "CH_A_OUT_A") (pintype "input"))
      (node (ref "R6") (pin "1") (pinfunction "1_1") (pintype "passive"))
    )
    (net (code "62") (name "Net-(PSG_1B-CH_B)") (class "Default")
      (node (ref "OUT_1") (pin "2") (pinfunction "2_2") (pintype "passive"))
      (node (ref "PSG_1") (pin "OUT_B") (pinfunction "CH_B_OUT_B") (pintype "input"))
      (node (ref "R7") (pin "1") (pinfunction "1_1") (pintype "passive"))
    )
    (net (code "63") (name "Net-(PSG_1B-CH_C)") (class "Default")
      (node (ref "OUT_1") (pin "3") (pinfunction "3_3") (pintype "passive"))
      (node (ref "PSG_1") (pin "OUT_C") (pinfunction "CH_C_OUT_C") (pintype "input"))
      (node (ref "R8") (pin "1") (pinfunction "1_1") (pintype "passive"))
    )
    (net (code "64") (name "Net-(PSG_2B-CH_A)") (class "Default")
      (node (ref "OUT_2") (pin "1") (pinfunction "1_1") (pintype "passive"))
      (node (ref "PSG_2") (pin "OUT_A") (pinfunction "CH_A_OUT_A") (pintype "input"))
      (node (ref "R11") (pin "1") (pinfunction "1_1") (pintype "passive"))
    )
    (net (code "65") (name "Net-(PSG_2B-CH_B)") (class "Default")
      (node (ref "OUT_2") (pin "2") (pinfunction "2_2") (pintype "passive"))
      (node (ref "PSG_2") (pin "OUT_B") (pinfunction "CH_B_OUT_B") (pintype "input"))
      (node (ref "R12") (pin "1") (pinfunction "1_1") (pintype "passive"))
    )
    (net (code "66") (name "Net-(PSG_2B-CH_C)") (class "Default")
      (node (ref "OUT_2") (pin "3") (pinfunction "3_3") (pintype "passive"))
      (node (ref "PSG_2") (pin "OUT_C") (pinfunction "CH_C_OUT_C") (pintype "input"))
      (node (ref "R13") (pin "1") (pinfunction "1_1") (pintype "passive"))
    )
    (net (code "67") (name "Net-(PSG_3B-CH_A)") (class "Default")
      (node (ref "OUT_3") (pin "1") (pinfunction "1_1") (pintype "passive"))
      (node (ref "PSG_3") (pin "OUT_A") (pinfunction "CH_A_OUT_A") (pintype "input"))
      (node (ref "R16") (pin "1") (pinfunction "1_1") (pintype "passive"))
    )
    (net (code "68") (name "Net-(PSG_3B-CH_B)") (class "Default")
      (node (ref "OUT_3") (pin "2") (pinfunction "2_2") (pintype "passive"))
      (node (ref "PSG_3") (pin "OUT_B") (pinfunction "CH_B_OUT_B") (pintype "input"))
      (node (ref "R17") (pin "1") (pinfunction "1_1") (pintype "passive"))
    )
    (net (code "69") (name "Net-(PSG_3B-CH_C)") (class "Default")
      (node (ref "OUT_3") (pin "3") (pinfunction "3_3") (pintype "passive"))
      (node (ref "PSG_3") (pin "OUT_C") (pinfunction "CH_C_OUT_C") (pintype "input"))
      (node (ref "R18") (pin "1") (pinfunction "1_1") (pintype "passive"))
    )
  )
)
